# 04_-_LCD_VGA.net
KiCad netlist of a schematic drawn in Altium Designer
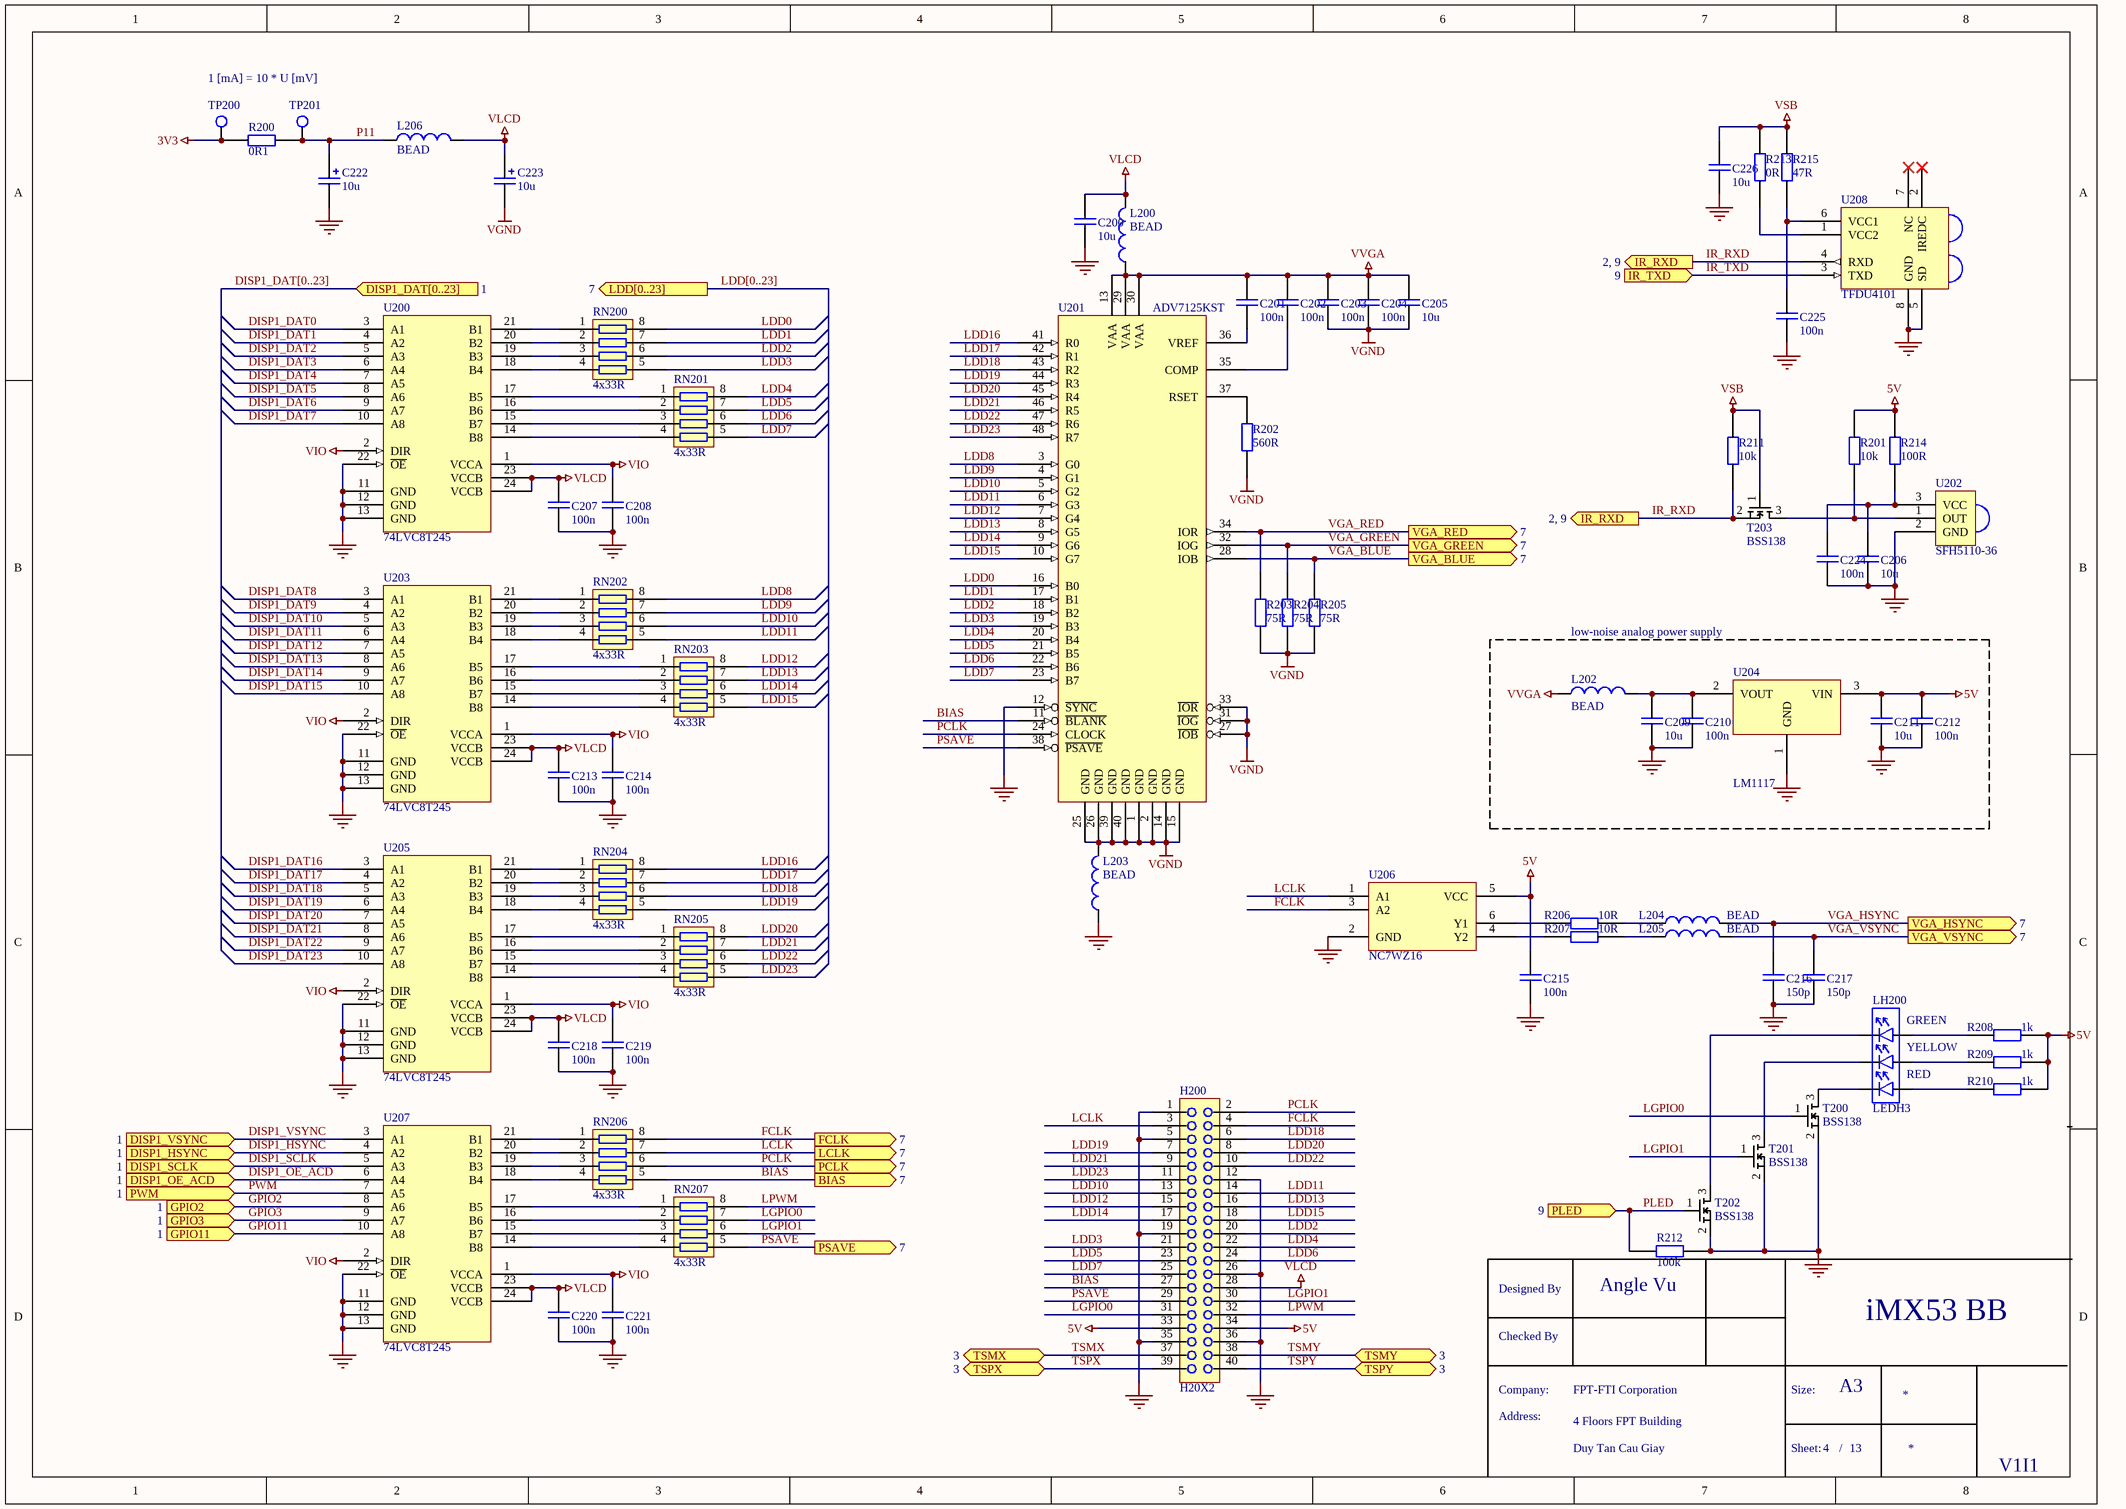
[diagram p0: [04] - LCD, VGA.SchDoc]

(export (version "E")
  (design (tool "Eeschema 10.0.6"))
  (components
    (comp (ref "C200") (value "10u") (footprint "0805") (libsource (lib "imxbb") (part "C")))
    (comp (ref "C201") (value "100n") (footprint "0603") (libsource (lib "imxbb") (part "C")))
    (comp (ref "C202") (value "100n") (footprint "0603") (libsource (lib "imxbb") (part "C")))
    (comp (ref "C203") (value "100n") (footprint "0603") (libsource (lib "imxbb") (part "C")))
    (comp (ref "C204") (value "100n") (footprint "0603") (libsource (lib "imxbb") (part "C")))
    (comp (ref "C205") (value "10u") (footprint "0805") (libsource (lib "imxbb") (part "C")))
    (comp (ref "C206") (value "10u") (footprint "0805") (libsource (lib "imxbb") (part "C")))
    (comp (ref "C207") (value "100n") (footprint "0603") (libsource (lib "imxbb") (part "C")))
    (comp (ref "C208") (value "100n") (footprint "0603") (libsource (lib "imxbb") (part "C")))
    (comp (ref "C209") (value "10u") (footprint "0805") (libsource (lib "imxbb") (part "C")))
    (comp (ref "C210") (value "100n") (footprint "0603") (libsource (lib "imxbb") (part "C")))
    (comp (ref "C211") (value "10u") (footprint "0805") (libsource (lib "imxbb") (part "C")))
    (comp (ref "C212") (value "100n") (footprint "0603") (libsource (lib "imxbb") (part "C")))
    (comp (ref "C213") (value "100n") (footprint "0603") (libsource (lib "imxbb") (part "C")))
    (comp (ref "C214") (value "100n") (footprint "0603") (libsource (lib "imxbb") (part "C")))
    (comp (ref "C215") (value "100n") (footprint "0603") (libsource (lib "imxbb") (part "C")))
    (comp (ref "C216") (value "150p") (footprint "0603") (libsource (lib "imxbb") (part "C")))
    (comp (ref "C217") (value "150p") (footprint "0603") (libsource (lib "imxbb") (part "C")))
    (comp (ref "C218") (value "100n") (footprint "0603") (libsource (lib "imxbb") (part "C")))
    (comp (ref "C219") (value "100n") (footprint "0603") (libsource (lib "imxbb") (part "C")))
    (comp (ref "C220") (value "100n") (footprint "0603") (libsource (lib "imxbb") (part "C")))
    (comp (ref "C221") (value "100n") (footprint "0603") (libsource (lib "imxbb") (part "C")))
    (comp (ref "C222") (value "10u") (footprint "3216A") (libsource (lib "imxbb") (part "C+")))
    (comp (ref "C223") (value "10u") (footprint "3216A") (libsource (lib "imxbb") (part "C+")))
    (comp (ref "C224") (value "100n") (footprint "0603") (libsource (lib "imxbb") (part "C")))
    (comp (ref "C225") (value "100n") (footprint "0603") (libsource (lib "imxbb") (part "C")))
    (comp (ref "C226") (value "10u") (footprint "0805") (libsource (lib "imxbb") (part "C")))
    (comp (ref "H200") (value "H20X2") (footprint "H2x20") (libsource (lib "imxbb") (part "H20X2")))
    (comp (ref "L200") (value "BEAD") (footprint "0603") (libsource (lib "imxbb") (part "FBEAD")))
    (comp (ref "L202") (value "BEAD") (footprint "0603") (libsource (lib "imxbb") (part "FBEAD")))
    (comp (ref "L203") (value "BEAD") (footprint "0603") (libsource (lib "imxbb") (part "FBEAD")))
    (comp (ref "L204") (value "BEAD") (footprint "0603") (libsource (lib "imxbb") (part "FBEAD")))
    (comp (ref "L205") (value "BEAD") (footprint "0603") (libsource (lib "imxbb") (part "FBEAD")))
    (comp (ref "L206") (value "BEAD") (footprint "0603") (libsource (lib "") (part "FBEAD_1")))
    (comp (ref "LH200") (value "LEDH3") (footprint "LED HOLDER 3") (libsource (lib "imxbb") (part "LEDH3")))
    (comp (ref "R200") (value "0R1") (footprint "0603") (libsource (lib "") (part "R_1")))
    (comp (ref "R201") (value "10k") (footprint "0603") (libsource (lib "") (part "R_3")))
    (comp (ref "R202") (value "560R") (footprint "0603") (libsource (lib "imxbb") (part "R")))
    (comp (ref "R203") (value "75R") (footprint "0603") (libsource (lib "imxbb") (part "R")))
    (comp (ref "R204") (value "75R") (footprint "0603") (libsource (lib "imxbb") (part "R")))
    (comp (ref "R205") (value "75R") (footprint "0603") (libsource (lib "imxbb") (part "R")))
    (comp (ref "R206") (value "10R") (footprint "0603") (libsource (lib "") (part "R_2")))
    (comp (ref "R207") (value "10R") (footprint "0603") (libsource (lib "") (part "R_2")))
    (comp (ref "R208") (value "1k") (footprint "0603") (libsource (lib "") (part "R_2")))
    (comp (ref "R209") (value "1k") (footprint "0603") (libsource (lib "") (part "R_2")))
    (comp (ref "R210") (value "1k") (footprint "0603") (libsource (lib "") (part "R_2")))
    (comp (ref "R211") (value "10k") (footprint "0603") (libsource (lib "") (part "R_3")))
    (comp (ref "R212") (value "100k") (footprint "0603") (libsource (lib "") (part "R_1")))
    (comp (ref "R213") (value "0R") (footprint "0603") (libsource (lib "imxbb") (part "R")))
    (comp (ref "R214") (value "100R") (footprint "0603") (libsource (lib "") (part "R_3")))
    (comp (ref "R215") (value "47R") (footprint "0603") (libsource (lib "") (part "R_3")))
    (comp (ref "RN200") (value "4x33R") (footprint "RX4_NS") (libsource (lib "imxbb") (part "RN4")))
    (comp (ref "RN201") (value "4x33R") (footprint "RX4_NS") (libsource (lib "imxbb") (part "RN4")))
    (comp (ref "RN202") (value "4x33R") (footprint "RX4_NS") (libsource (lib "imxbb") (part "RN4")))
    (comp (ref "RN203") (value "4x33R") (footprint "RX4_NS") (libsource (lib "imxbb") (part "RN4")))
    (comp (ref "RN204") (value "4x33R") (footprint "RX4_NS") (libsource (lib "imxbb") (part "RN4")))
    (comp (ref "RN205") (value "4x33R") (footprint "RX4_NS") (libsource (lib "imxbb") (part "RN4")))
    (comp (ref "RN206") (value "4x33R") (footprint "RX4_NS") (libsource (lib "imxbb") (part "RN4")))
    (comp (ref "RN207") (value "4x33R") (footprint "RX4_NS") (libsource (lib "imxbb") (part "RN4")))
    (comp (ref "T200") (value "BSS138") (footprint "SOT23") (libsource (lib "imxbb") (part "BSS138")))
    (comp (ref "T201") (value "BSS138") (footprint "SOT23") (libsource (lib "imxbb") (part "BSS138")))
    (comp (ref "T202") (value "BSS138") (footprint "SOT23") (libsource (lib "imxbb") (part "BSS138")))
    (comp (ref "T203") (value "BSS138") (footprint "SOT23") (libsource (lib "imxbb") (part "BSS138")))
    (comp (ref "TP200")
      (value "TESTPOINT")
      (footprint "TESTPOINT_2mm")
      (description "Testpoint pad")
      (libsource (lib "imxbb") (part "TESTPOINT"))
    )
    (comp (ref "TP201")
      (value "TESTPOINT")
      (footprint "TESTPOINT_2mm")
      (description "Testpoint pad")
      (libsource (lib "imxbb") (part "TESTPOINT"))
    )
    (comp (ref "U200")
      (value "74LVC8T245")
      (footprint "TSSOP24")
      (libsource (lib "imxbb") (part "74LVC8T245"))
    )
    (comp (ref "U201") (value "ADV7125KST") (footprint "LQFP48") (libsource (lib "imxbb") (part "ADV7125")))
    (comp (ref "U202") (value "SFH5110-36") (footprint "SFH511x") (libsource (lib "imxbb") (part "SFH5110")))
    (comp (ref "U203")
      (value "74LVC8T245")
      (footprint "TSSOP24")
      (libsource (lib "imxbb") (part "74LVC8T245"))
    )
    (comp (ref "U204") (value "LM1117") (footprint "SOT223") (libsource (lib "imxbb") (part "LM1117")))
    (comp (ref "U205")
      (value "74LVC8T245")
      (footprint "TSSOP24")
      (libsource (lib "imxbb") (part "74LVC8T245"))
    )
    (comp (ref "U206") (value "NC7WZ16") (footprint "SC70") (libsource (lib "imxbb") (part "NC7WZ16")))
    (comp (ref "U207")
      (value "74LVC8T245")
      (footprint "TSSOP24")
      (libsource (lib "imxbb") (part "74LVC8T245"))
    )
    (comp (ref "U208") (value "TFDU4101") (footprint "TDFU4101") (libsource (lib "imxbb") (part "TFDU4101")))
  )
  (nets
    (net (code "1") (name "/BIAS") (class "Default")
      (node (ref "H200") (pin "27") (pinfunction "27_27") (pintype "passive"))
      (node (ref "RN206") (pin "5") (pintype "passive"))
      (node (ref "U201") (pin "11") (pinfunction "~{BLANK}_11") (pintype "input"))
    )
    (net (code "2") (name "/DISP1_DAT0") (class "Default")
      (node (ref "U200") (pin "3") (pinfunction "A1_3") (pintype "passive"))
    )
    (net (code "3") (name "/DISP1_DAT1") (class "Default")
      (node (ref "U200") (pin "4") (pinfunction "A2_4") (pintype "passive"))
    )
    (net (code "4") (name "/DISP1_DAT2") (class "Default")
      (node (ref "U200") (pin "5") (pinfunction "A3_5") (pintype "passive"))
    )
    (net (code "5") (name "/DISP1_DAT3") (class "Default")
      (node (ref "U200") (pin "6") (pinfunction "A4_6") (pintype "passive"))
    )
    (net (code "6") (name "/DISP1_DAT4") (class "Default")
      (node (ref "U200") (pin "7") (pinfunction "A5_7") (pintype "passive"))
    )
    (net (code "7") (name "/DISP1_DAT5") (class "Default")
      (node (ref "U200") (pin "8") (pinfunction "A6_8") (pintype "passive"))
    )
    (net (code "8") (name "/DISP1_DAT6") (class "Default")
      (node (ref "U200") (pin "9") (pinfunction "A7_9") (pintype "passive"))
    )
    (net (code "9") (name "/DISP1_DAT7") (class "Default")
      (node (ref "U200") (pin "10") (pinfunction "A8_10") (pintype "passive"))
    )
    (net (code "10") (name "/DISP1_DAT8") (class "Default")
      (node (ref "U203") (pin "3") (pinfunction "A1_3") (pintype "passive"))
    )
    (net (code "11") (name "/DISP1_DAT9") (class "Default")
      (node (ref "U203") (pin "4") (pinfunction "A2_4") (pintype "passive"))
    )
    (net (code "12") (name "/DISP1_DAT10") (class "Default")
      (node (ref "U203") (pin "5") (pinfunction "A3_5") (pintype "passive"))
    )
    (net (code "13") (name "/DISP1_DAT11") (class "Default")
      (node (ref "U203") (pin "6") (pinfunction "A4_6") (pintype "passive"))
    )
    (net (code "14") (name "/DISP1_DAT12") (class "Default")
      (node (ref "U203") (pin "7") (pinfunction "A5_7") (pintype "passive"))
    )
    (net (code "15") (name "/DISP1_DAT13") (class "Default")
      (node (ref "U203") (pin "8") (pinfunction "A6_8") (pintype "passive"))
    )
    (net (code "16") (name "/DISP1_DAT14") (class "Default")
      (node (ref "U203") (pin "9") (pinfunction "A7_9") (pintype "passive"))
    )
    (net (code "17") (name "/DISP1_DAT15") (class "Default")
      (node (ref "U203") (pin "10") (pinfunction "A8_10") (pintype "passive"))
    )
    (net (code "18") (name "/DISP1_DAT16") (class "Default")
      (node (ref "U205") (pin "3") (pinfunction "A1_3") (pintype "passive"))
    )
    (net (code "19") (name "/DISP1_DAT17") (class "Default")
      (node (ref "U205") (pin "4") (pinfunction "A2_4") (pintype "passive"))
    )
    (net (code "20") (name "/DISP1_DAT18") (class "Default")
      (node (ref "U205") (pin "5") (pinfunction "A3_5") (pintype "passive"))
    )
    (net (code "21") (name "/DISP1_DAT19") (class "Default")
      (node (ref "U205") (pin "6") (pinfunction "A4_6") (pintype "passive"))
    )
    (net (code "22") (name "/DISP1_DAT20") (class "Default")
      (node (ref "U205") (pin "7") (pinfunction "A5_7") (pintype "passive"))
    )
    (net (code "23") (name "/DISP1_DAT21") (class "Default")
      (node (ref "U205") (pin "8") (pinfunction "A6_8") (pintype "passive"))
    )
    (net (code "24") (name "/DISP1_DAT22") (class "Default")
      (node (ref "U205") (pin "9") (pinfunction "A7_9") (pintype "passive"))
    )
    (net (code "25") (name "/DISP1_DAT23") (class "Default")
      (node (ref "U205") (pin "10") (pinfunction "A8_10") (pintype "passive"))
    )
    (net (code "27") (name "/DISP1_HSYNC") (class "Default")
      (node (ref "U207") (pin "4") (pinfunction "A2_4") (pintype "passive"))
    )
    (net (code "28") (name "/DISP1_OE_ACD") (class "Default")
      (node (ref "U207") (pin "6") (pinfunction "A4_6") (pintype "passive"))
    )
    (net (code "29") (name "/DISP1_SCLK") (class "Default")
      (node (ref "U207") (pin "5") (pinfunction "A3_5") (pintype "passive"))
    )
    (net (code "30") (name "/DISP1_VSYNC") (class "Default")
      (node (ref "U207") (pin "3") (pinfunction "A1_3") (pintype "passive"))
    )
    (net (code "31") (name "/FCLK") (class "Default")
      (node (ref "H200") (pin "4") (pinfunction "4_4") (pintype "passive"))
      (node (ref "RN206") (pin "8") (pintype "passive"))
      (node (ref "U206") (pin "3") (pinfunction "A2_3") (pintype "passive"))
    )
    (net (code "32") (name "/GPIO2") (class "Default")
      (node (ref "U207") (pin "8") (pinfunction "A6_8") (pintype "passive"))
    )
    (net (code "33") (name "/GPIO3") (class "Default")
      (node (ref "U207") (pin "9") (pinfunction "A7_9") (pintype "passive"))
    )
    (net (code "34") (name "/GPIO11") (class "Default")
      (node (ref "U207") (pin "10") (pinfunction "A8_10") (pintype "passive"))
    )
    (net (code "35") (name "/IR_RXD") (class "Default")
      (node (ref "R211") (pin "2") (pinfunction "2_2") (pintype "passive"))
      (node (ref "T203") (pin "2") (pinfunction "S_2") (pintype "passive"))
      (node (ref "U208") (pin "4") (pinfunction "RXD_4") (pintype "output"))
    )
    (net (code "36") (name "/IR_TXD") (class "Default")
      (node (ref "U208") (pin "3") (pinfunction "TXD_3") (pintype "input"))
    )
    (net (code "37") (name "/LCLK") (class "Default")
      (node (ref "H200") (pin "3") (pinfunction "3_3") (pintype "passive"))
      (node (ref "RN206") (pin "7") (pintype "passive"))
      (node (ref "U206") (pin "1") (pinfunction "A1_1") (pintype "passive"))
    )
    (net (code "38") (name "/LDD0") (class "Default")
      (node (ref "RN200") (pin "8") (pintype "passive"))
      (node (ref "U201") (pin "16") (pinfunction "B0_16") (pintype "input"))
    )
    (net (code "39") (name "/LDD1") (class "Default")
      (node (ref "RN200") (pin "7") (pintype "passive"))
      (node (ref "U201") (pin "17") (pinfunction "B1_17") (pintype "input"))
    )
    (net (code "40") (name "/LDD2") (class "Default")
      (node (ref "H200") (pin "20") (pinfunction "20_20") (pintype "passive"))
      (node (ref "RN200") (pin "6") (pintype "passive"))
      (node (ref "U201") (pin "18") (pinfunction "B2_18") (pintype "input"))
    )
    (net (code "41") (name "/LDD3") (class "Default")
      (node (ref "H200") (pin "21") (pinfunction "21_21") (pintype "passive"))
      (node (ref "RN200") (pin "5") (pintype "passive"))
      (node (ref "U201") (pin "19") (pinfunction "B3_19") (pintype "input"))
    )
    (net (code "42") (name "/LDD4") (class "Default")
      (node (ref "H200") (pin "22") (pinfunction "22_22") (pintype "passive"))
      (node (ref "RN201") (pin "8") (pintype "passive"))
      (node (ref "U201") (pin "20") (pinfunction "B4_20") (pintype "input"))
    )
    (net (code "43") (name "/LDD5") (class "Default")
      (node (ref "H200") (pin "23") (pinfunction "23_23") (pintype "passive"))
      (node (ref "RN201") (pin "7") (pintype "passive"))
      (node (ref "U201") (pin "21") (pinfunction "B5_21") (pintype "input"))
    )
    (net (code "44") (name "/LDD6") (class "Default")
      (node (ref "H200") (pin "24") (pinfunction "24_24") (pintype "passive"))
      (node (ref "RN201") (pin "6") (pintype "passive"))
      (node (ref "U201") (pin "22") (pinfunction "B6_22") (pintype "input"))
    )
    (net (code "45") (name "/LDD7") (class "Default")
      (node (ref "H200") (pin "25") (pinfunction "25_25") (pintype "passive"))
      (node (ref "RN201") (pin "5") (pintype "passive"))
      (node (ref "U201") (pin "23") (pinfunction "B7_23") (pintype "input"))
    )
    (net (code "46") (name "/LDD8") (class "Default")
      (node (ref "RN202") (pin "8") (pintype "passive"))
      (node (ref "U201") (pin "3") (pinfunction "G0_3") (pintype "input"))
    )
    (net (code "47") (name "/LDD9") (class "Default")
      (node (ref "RN202") (pin "7") (pintype "passive"))
      (node (ref "U201") (pin "4") (pinfunction "G1_4") (pintype "input"))
    )
    (net (code "48") (name "/LDD10") (class "Default")
      (node (ref "H200") (pin "13") (pinfunction "13_13") (pintype "passive"))
      (node (ref "RN202") (pin "6") (pintype "passive"))
      (node (ref "U201") (pin "5") (pinfunction "G2_5") (pintype "input"))
    )
    (net (code "49") (name "/LDD11") (class "Default")
      (node (ref "H200") (pin "14") (pinfunction "14_14") (pintype "passive"))
      (node (ref "RN202") (pin "5") (pintype "passive"))
      (node (ref "U201") (pin "6") (pinfunction "G3_6") (pintype "input"))
    )
    (net (code "50") (name "/LDD12") (class "Default")
      (node (ref "H200") (pin "15") (pinfunction "15_15") (pintype "passive"))
      (node (ref "RN203") (pin "8") (pintype "passive"))
      (node (ref "U201") (pin "7") (pinfunction "G4_7") (pintype "input"))
    )
    (net (code "51") (name "/LDD13") (class "Default")
      (node (ref "H200") (pin "16") (pinfunction "16_16") (pintype "passive"))
      (node (ref "RN203") (pin "7") (pintype "passive"))
      (node (ref "U201") (pin "8") (pinfunction "G5_8") (pintype "input"))
    )
    (net (code "52") (name "/LDD14") (class "Default")
      (node (ref "H200") (pin "17") (pinfunction "17_17") (pintype "passive"))
      (node (ref "RN203") (pin "6") (pintype "passive"))
      (node (ref "U201") (pin "9") (pinfunction "G6_9") (pintype "input"))
    )
    (net (code "53") (name "/LDD15") (class "Default")
      (node (ref "H200") (pin "18") (pinfunction "18_18") (pintype "passive"))
      (node (ref "RN203") (pin "5") (pintype "passive"))
      (node (ref "U201") (pin "10") (pinfunction "G7_10") (pintype "input"))
    )
    (net (code "54") (name "/LDD16") (class "Default")
      (node (ref "RN204") (pin "8") (pintype "passive"))
      (node (ref "U201") (pin "41") (pinfunction "R0_41") (pintype "input"))
    )
    (net (code "55") (name "/LDD17") (class "Default")
      (node (ref "RN204") (pin "7") (pintype "passive"))
      (node (ref "U201") (pin "42") (pinfunction "R1_42") (pintype "input"))
    )
    (net (code "56") (name "/LDD18") (class "Default")
      (node (ref "H200") (pin "6") (pinfunction "6_6") (pintype "passive"))
      (node (ref "RN204") (pin "6") (pintype "passive"))
      (node (ref "U201") (pin "43") (pinfunction "R2_43") (pintype "input"))
    )
    (net (code "57") (name "/LDD19") (class "Default")
      (node (ref "H200") (pin "7") (pinfunction "7_7") (pintype "passive"))
      (node (ref "RN204") (pin "5") (pintype "passive"))
      (node (ref "U201") (pin "44") (pinfunction "R3_44") (pintype "input"))
    )
    (net (code "58") (name "/LDD20") (class "Default")
      (node (ref "H200") (pin "8") (pinfunction "8_8") (pintype "passive"))
      (node (ref "RN205") (pin "8") (pintype "passive"))
      (node (ref "U201") (pin "45") (pinfunction "R4_45") (pintype "input"))
    )
    (net (code "59") (name "/LDD21") (class "Default")
      (node (ref "H200") (pin "9") (pinfunction "9_9") (pintype "passive"))
      (node (ref "RN205") (pin "7") (pintype "passive"))
      (node (ref "U201") (pin "46") (pinfunction "R5_46") (pintype "input"))
    )
    (net (code "60") (name "/LDD22") (class "Default")
      (node (ref "H200") (pin "10") (pinfunction "10_10") (pintype "passive"))
      (node (ref "RN205") (pin "6") (pintype "passive"))
      (node (ref "U201") (pin "47") (pinfunction "R6_47") (pintype "input"))
    )
    (net (code "61") (name "/LDD23") (class "Default")
      (node (ref "H200") (pin "11") (pinfunction "11_11") (pintype "passive"))
      (node (ref "RN205") (pin "5") (pintype "passive"))
      (node (ref "U201") (pin "48") (pinfunction "R7_48") (pintype "input"))
    )
    (net (code "63") (name "/LGPIO0") (class "Default")
      (node (ref "H200") (pin "31") (pinfunction "31_31") (pintype "passive"))
      (node (ref "RN207") (pin "7") (pintype "passive"))
      (node (ref "T200") (pin "1") (pinfunction "G_1") (pintype "passive"))
    )
    (net (code "64") (name "/LGPIO1") (class "Default")
      (node (ref "H200") (pin "30") (pinfunction "30_30") (pintype "passive"))
      (node (ref "RN207") (pin "6") (pintype "passive"))
      (node (ref "T201") (pin "1") (pinfunction "G_1") (pintype "passive"))
    )
    (net (code "65") (name "/LPWM") (class "Default")
      (node (ref "H200") (pin "32") (pinfunction "32_32") (pintype "passive"))
      (node (ref "RN207") (pin "8") (pintype "passive"))
    )
    (net (code "66") (name "/P11") (class "Default")
      (node (ref "C222") (pin "1") (pinfunction "1_1") (pintype "passive"))
      (node (ref "L206") (pin "2") (pinfunction "2_2") (pintype "passive"))
      (node (ref "R200") (pin "2") (pinfunction "2_2") (pintype "passive"))
      (node (ref "TP201") (pin "1") (pinfunction "1_1") (pintype "passive"))
    )
    (net (code "67") (name "/PCLK") (class "Default")
      (node (ref "H200") (pin "2") (pinfunction "2_2") (pintype "passive"))
      (node (ref "RN206") (pin "6") (pintype "passive"))
      (node (ref "U201") (pin "24") (pinfunction "CLOCK_24") (pintype "input"))
    )
    (net (code "68") (name "/PLED") (class "Default")
      (node (ref "R212") (pin "1") (pinfunction "1_1") (pintype "passive"))
      (node (ref "T202") (pin "1") (pinfunction "G_1") (pintype "passive"))
    )
    (net (code "69") (name "/PSAVE") (class "Default")
      (node (ref "H200") (pin "29") (pinfunction "29_29") (pintype "passive"))
      (node (ref "RN207") (pin "5") (pintype "passive"))
      (node (ref "U201") (pin "38") (pinfunction "~{PSAVE}_38") (pintype "input"))
    )
    (net (code "70") (name "/PWM") (class "Default")
      (node (ref "U207") (pin "7") (pinfunction "A5_7") (pintype "passive"))
    )
    (net (code "71") (name "/TSMX") (class "Default")
      (node (ref "H200") (pin "37") (pinfunction "37_37") (pintype "passive"))
    )
    (net (code "72") (name "/TSMY") (class "Default")
      (node (ref "H200") (pin "38") (pinfunction "38_38") (pintype "passive"))
    )
    (net (code "73") (name "/TSPX") (class "Default")
      (node (ref "H200") (pin "39") (pinfunction "39_39") (pintype "passive"))
    )
    (net (code "74") (name "/TSPY") (class "Default")
      (node (ref "H200") (pin "40") (pinfunction "40_40") (pintype "passive"))
    )
    (net (code "75") (name "/VGA_BLUE") (class "Default")
      (node (ref "R205") (pin "2") (pinfunction "2_2") (pintype "passive"))
      (node (ref "U201") (pin "28") (pinfunction "IOB_28") (pintype "output"))
    )
    (net (code "76") (name "/VGA_GREEN") (class "Default")
      (node (ref "R204") (pin "2") (pinfunction "2_2") (pintype "passive"))
      (node (ref "U201") (pin "32") (pinfunction "IOG_32") (pintype "output"))
    )
    (net (code "77") (name "/VGA_HSYNC") (class "Default")
      (node (ref "C216") (pin "2") (pinfunction "2_2") (pintype "passive"))
      (node (ref "L204") (pin "2") (pinfunction "2_2") (pintype "passive"))
    )
    (net (code "78") (name "/VGA_RED") (class "Default")
      (node (ref "R203") (pin "2") (pinfunction "2_2") (pintype "passive"))
      (node (ref "U201") (pin "34") (pinfunction "IOR_34") (pintype "output"))
    )
    (net (code "79") (name "/VGA_VSYNC") (class "Default")
      (node (ref "C217") (pin "2") (pinfunction "2_2") (pintype "passive"))
      (node (ref "L205") (pin "2") (pinfunction "2_2") (pintype "passive"))
    )
    (net (code "80") (name "3V3") (class "Default")
      (node (ref "R200") (pin "1") (pinfunction "1_1") (pintype "passive"))
      (node (ref "TP200") (pin "1") (pinfunction "1_1") (pintype "passive"))
    )
    (net (code "81") (name "5V") (class "Default")
      (node (ref "C211") (pin "2") (pinfunction "2_2") (pintype "passive"))
      (node (ref "C212") (pin "2") (pinfunction "2_2") (pintype "passive"))
      (node (ref "C215") (pin "2") (pinfunction "2_2") (pintype "passive"))
      (node (ref "H200") (pin "33") (pinfunction "33_33") (pintype "passive"))
      (node (ref "H200") (pin "34") (pinfunction "34_34") (pintype "passive"))
      (node (ref "R201") (pin "1") (pinfunction "1_1") (pintype "passive"))
      (node (ref "R208") (pin "1") (pinfunction "1_1") (pintype "passive"))
      (node (ref "R209") (pin "1") (pinfunction "1_1") (pintype "passive"))
      (node (ref "R210") (pin "1") (pinfunction "1_1") (pintype "passive"))
      (node (ref "R214") (pin "1") (pinfunction "1_1") (pintype "passive"))
      (node (ref "U204") (pin "3") (pinfunction "VIN_3") (pintype "passive"))
      (node (ref "U206") (pin "5") (pinfunction "VCC_5") (pintype "passive"))
    )
    (net (code "82") (name "GND") (class "Default")
      (node (ref "C200") (pin "1") (pinfunction "1_1") (pintype "passive"))
      (node (ref "C206") (pin "1") (pinfunction "1_1") (pintype "passive"))
      (node (ref "C207") (pin "1") (pinfunction "1_1") (pintype "passive"))
      (node (ref "C208") (pin "1") (pinfunction "1_1") (pintype "passive"))
      (node (ref "C209") (pin "1") (pinfunction "1_1") (pintype "passive"))
      (node (ref "C210") (pin "1") (pinfunction "1_1") (pintype "passive"))
      (node (ref "C211") (pin "1") (pinfunction "1_1") (pintype "passive"))
      (node (ref "C212") (pin "1") (pinfunction "1_1") (pintype "passive"))
      (node (ref "C213") (pin "1") (pinfunction "1_1") (pintype "passive"))
      (node (ref "C214") (pin "1") (pinfunction "1_1") (pintype "passive"))
      (node (ref "C215") (pin "1") (pinfunction "1_1") (pintype "passive"))
      (node (ref "C216") (pin "1") (pinfunction "1_1") (pintype "passive"))
      (node (ref "C217") (pin "1") (pinfunction "1_1") (pintype "passive"))
      (node (ref "C218") (pin "1") (pinfunction "1_1") (pintype "passive"))
      (node (ref "C219") (pin "1") (pinfunction "1_1") (pintype "passive"))
      (node (ref "C220") (pin "1") (pinfunction "1_1") (pintype "passive"))
      (node (ref "C221") (pin "1") (pinfunction "1_1") (pintype "passive"))
      (node (ref "C222") (pin "2") (pinfunction "2_2") (pintype "passive"))
      (node (ref "C224") (pin "1") (pinfunction "1_1") (pintype "passive"))
      (node (ref "C225") (pin "1") (pinfunction "1_1") (pintype "passive"))
      (node (ref "C226") (pin "1") (pinfunction "1_1") (pintype "passive"))
      (node (ref "H200") (pin "1") (pinfunction "1_1") (pintype "passive"))
      (node (ref "H200") (pin "12") (pinfunction "12_12") (pintype "passive"))
      (node (ref "H200") (pin "19") (pinfunction "19_19") (pintype "passive"))
      (node (ref "H200") (pin "26") (pinfunction "26_26") (pintype "passive"))
      (node (ref "H200") (pin "35") (pinfunction "35_35") (pintype "passive"))
      (node (ref "H200") (pin "36") (pinfunction "36_36") (pintype "passive"))
      (node (ref "H200") (pin "5") (pinfunction "5_5") (pintype "passive"))
      (node (ref "L203") (pin "1") (pinfunction "1_1") (pintype "passive"))
      (node (ref "R212") (pin "2") (pinfunction "2_2") (pintype "passive"))
      (node (ref "T200") (pin "2") (pinfunction "S_2") (pintype "passive"))
      (node (ref "T201") (pin "2") (pinfunction "S_2") (pintype "passive"))
      (node (ref "T202") (pin "2") (pinfunction "S_2") (pintype "passive"))
      (node (ref "U200") (pin "11") (pinfunction "GND_11") (pintype "power_in"))
      (node (ref "U200") (pin "12") (pinfunction "GND_12") (pintype "power_in"))
      (node (ref "U200") (pin "13") (pinfunction "GND_13") (pintype "power_in"))
      (node (ref "U200") (pin "22") (pinfunction "~{OE}_22") (pintype "input"))
      (node (ref "U201") (pin "12") (pinfunction "~{SYNC}_12") (pintype "input"))
      (node (ref "U202") (pin "2") (pinfunction "GND_2") (pintype "passive"))
      (node (ref "U203") (pin "11") (pinfunction "GND_11") (pintype "power_in"))
      (node (ref "U203") (pin "12") (pinfunction "GND_12") (pintype "power_in"))
      (node (ref "U203") (pin "13") (pinfunction "GND_13") (pintype "power_in"))
      (node (ref "U203") (pin "22") (pinfunction "~{OE}_22") (pintype "input"))
      (node (ref "U204") (pin "1") (pinfunction "GND_1") (pintype "passive"))
      (node (ref "U205") (pin "11") (pinfunction "GND_11") (pintype "power_in"))
      (node (ref "U205") (pin "12") (pinfunction "GND_12") (pintype "power_in"))
      (node (ref "U205") (pin "13") (pinfunction "GND_13") (pintype "power_in"))
      (node (ref "U205") (pin "22") (pinfunction "~{OE}_22") (pintype "input"))
      (node (ref "U206") (pin "2") (pinfunction "GND_2") (pintype "passive"))
      (node (ref "U207") (pin "11") (pinfunction "GND_11") (pintype "power_in"))
      (node (ref "U207") (pin "12") (pinfunction "GND_12") (pintype "power_in"))
      (node (ref "U207") (pin "13") (pinfunction "GND_13") (pintype "power_in"))
      (node (ref "U207") (pin "22") (pinfunction "~{OE}_22") (pintype "input"))
      (node (ref "U208") (pin "5") (pinfunction "SD_5") (pintype "passive"))
      (node (ref "U208") (pin "8") (pinfunction "GND_8") (pintype "passive"))
    )
    (net (code "83") (name "Net-(L204-Pad1)") (class "Default")
      (node (ref "L204") (pin "1") (pinfunction "1_1") (pintype "passive"))
      (node (ref "R206") (pin "1") (pinfunction "1_1") (pintype "passive"))
    )
    (net (code "84") (name "Net-(L205-Pad1)") (class "Default")
      (node (ref "L205") (pin "1") (pinfunction "1_1") (pintype "passive"))
      (node (ref "R207") (pin "1") (pinfunction "1_1") (pintype "passive"))
    )
    (net (code "85") (name "Net-(LH200-Pad2)") (class "Default")
      (node (ref "LH200") (pin "2") (pinfunction "2_2") (pintype "passive"))
      (node (ref "R208") (pin "2") (pinfunction "2_2") (pintype "passive"))
    )
    (net (code "86") (name "Net-(LH200-Pad4)") (class "Default")
      (node (ref "LH200") (pin "4") (pinfunction "4_4") (pintype "passive"))
      (node (ref "R209") (pin "2") (pinfunction "2_2") (pintype "passive"))
    )
    (net (code "87") (name "Net-(LH200-Pad6)") (class "Default")
      (node (ref "LH200") (pin "6") (pinfunction "6_6") (pintype "passive"))
      (node (ref "R210") (pin "2") (pinfunction "2_2") (pintype "passive"))
    )
    (net (code "88") (name "Net-(T200-D)") (class "Default")
      (node (ref "LH200") (pin "5") (pinfunction "5_5") (pintype "passive"))
      (node (ref "T200") (pin "3") (pinfunction "D_3") (pintype "passive"))
    )
    (net (code "89") (name "Net-(T201-D)") (class "Default")
      (node (ref "LH200") (pin "3") (pinfunction "3_3") (pintype "passive"))
      (node (ref "T201") (pin "3") (pinfunction "D_3") (pintype "passive"))
    )
    (net (code "90") (name "Net-(T202-D)") (class "Default")
      (node (ref "LH200") (pin "1") (pinfunction "1_1") (pintype "passive"))
      (node (ref "T202") (pin "3") (pinfunction "D_3") (pintype "passive"))
    )
    (net (code "91") (name "Net-(T203-D)") (class "Default")
      (node (ref "R201") (pin "2") (pinfunction "2_2") (pintype "passive"))
      (node (ref "T203") (pin "3") (pinfunction "D_3") (pintype "passive"))
      (node (ref "U202") (pin "1") (pinfunction "OUT_1") (pintype "passive"))
    )
    (net (code "92") (name "Net-(U200-B1)") (class "Default")
      (node (ref "RN200") (pin "1") (pintype "passive"))
      (node (ref "U200") (pin "21") (pinfunction "B1_21") (pintype "passive"))
    )
    (net (code "93") (name "Net-(U200-B2)") (class "Default")
      (node (ref "RN200") (pin "2") (pintype "passive"))
      (node (ref "U200") (pin "20") (pinfunction "B2_20") (pintype "passive"))
    )
    (net (code "94") (name "Net-(U200-B3)") (class "Default")
      (node (ref "RN200") (pin "3") (pintype "passive"))
      (node (ref "U200") (pin "19") (pinfunction "B3_19") (pintype "passive"))
    )
    (net (code "95") (name "Net-(U200-B4)") (class "Default")
      (node (ref "RN200") (pin "4") (pintype "passive"))
      (node (ref "U200") (pin "18") (pinfunction "B4_18") (pintype "passive"))
    )
    (net (code "96") (name "Net-(U200-B5)") (class "Default")
      (node (ref "RN201") (pin "1") (pintype "passive"))
      (node (ref "U200") (pin "17") (pinfunction "B5_17") (pintype "passive"))
    )
    (net (code "97") (name "Net-(U200-B6)") (class "Default")
      (node (ref "RN201") (pin "2") (pintype "passive"))
      (node (ref "U200") (pin "16") (pinfunction "B6_16") (pintype "passive"))
    )
    (net (code "98") (name "Net-(U200-B7)") (class "Default")
      (node (ref "RN201") (pin "3") (pintype "passive"))
      (node (ref "U200") (pin "15") (pinfunction "B7_15") (pintype "passive"))
    )
    (net (code "99") (name "Net-(U200-B8)") (class "Default")
      (node (ref "RN201") (pin "4") (pintype "passive"))
      (node (ref "U200") (pin "14") (pinfunction "B8_14") (pintype "passive"))
    )
    (net (code "100") (name "Net-(U201-COMP)") (class "Default")
      (node (ref "C202") (pin "1") (pinfunction "1_1") (pintype "passive"))
      (node (ref "U201") (pin "35") (pinfunction "COMP_35") (pintype "passive"))
    )
    (net (code "101") (name "Net-(U201-RSET)") (class "Default")
      (node (ref "R202") (pin "2") (pinfunction "2_2") (pintype "passive"))
      (node (ref "U201") (pin "37") (pinfunction "RSET_37") (pintype "passive"))
    )
    (net (code "102") (name "Net-(U201-VREF)") (class "Default")
      (node (ref "C201") (pin "1") (pinfunction "1_1") (pintype "passive"))
      (node (ref "U201") (pin "36") (pinfunction "VREF_36") (pintype "passive"))
    )
    (net (code "103") (name "Net-(U202-VCC)") (class "Default")
      (node (ref "C206") (pin "2") (pinfunction "2_2") (pintype "passive"))
      (node (ref "C224") (pin "2") (pinfunction "2_2") (pintype "passive"))
      (node (ref "R214") (pin "2") (pinfunction "2_2") (pintype "passive"))
      (node (ref "U202") (pin "3") (pinfunction "VCC_3") (pintype "passive"))
    )
    (net (code "104") (name "Net-(U203-B1)") (class "Default")
      (node (ref "RN202") (pin "1") (pintype "passive"))
      (node (ref "U203") (pin "21") (pinfunction "B1_21") (pintype "passive"))
    )
    (net (code "105") (name "Net-(U203-B2)") (class "Default")
      (node (ref "RN202") (pin "2") (pintype "passive"))
      (node (ref "U203") (pin "20") (pinfunction "B2_20") (pintype "passive"))
    )
    (net (code "106") (name "Net-(U203-B3)") (class "Default")
      (node (ref "RN202") (pin "3") (pintype "passive"))
      (node (ref "U203") (pin "19") (pinfunction "B3_19") (pintype "passive"))
    )
    (net (code "107") (name "Net-(U203-B4)") (class "Default")
      (node (ref "RN202") (pin "4") (pintype "passive"))
      (node (ref "U203") (pin "18") (pinfunction "B4_18") (pintype "passive"))
    )
    (net (code "108") (name "Net-(U203-B5)") (class "Default")
      (node (ref "RN203") (pin "1") (pintype "passive"))
      (node (ref "U203") (pin "17") (pinfunction "B5_17") (pintype "passive"))
    )
    (net (code "109") (name "Net-(U203-B6)") (class "Default")
      (node (ref "RN203") (pin "2") (pintype "passive"))
      (node (ref "U203") (pin "16") (pinfunction "B6_16") (pintype "passive"))
    )
    (net (code "110") (name "Net-(U203-B7)") (class "Default")
      (node (ref "RN203") (pin "3") (pintype "passive"))
      (node (ref "U203") (pin "15") (pinfunction "B7_15") (pintype "passive"))
    )
    (net (code "111") (name "Net-(U203-B8)") (class "Default")
      (node (ref "RN203") (pin "4") (pintype "passive"))
      (node (ref "U203") (pin "14") (pinfunction "B8_14") (pintype "passive"))
    )
    (net (code "112") (name "Net-(U204-VOUT)") (class "Default")
      (node (ref "C209") (pin "2") (pinfunction "2_2") (pintype "passive"))
      (node (ref "C210") (pin "2") (pinfunction "2_2") (pintype "passive"))
      (node (ref "L202") (pin "2") (pinfunction "2_2") (pintype "passive"))
      (node (ref "U204") (pin "2") (pinfunction "VOUT_2") (pintype "passive"))
    )
    (net (code "113") (name "Net-(U205-B1)") (class "Default")
      (node (ref "RN204") (pin "1") (pintype "passive"))
      (node (ref "U205") (pin "21") (pinfunction "B1_21") (pintype "passive"))
    )
    (net (code "114") (name "Net-(U205-B2)") (class "Default")
      (node (ref "RN204") (pin "2") (pintype "passive"))
      (node (ref "U205") (pin "20") (pinfunction "B2_20") (pintype "passive"))
    )
    (net (code "115") (name "Net-(U205-B3)") (class "Default")
      (node (ref "RN204") (pin "3") (pintype "passive"))
      (node (ref "U205") (pin "19") (pinfunction "B3_19") (pintype "passive"))
    )
    (net (code "116") (name "Net-(U205-B4)") (class "Default")
      (node (ref "RN204") (pin "4") (pintype "passive"))
      (node (ref "U205") (pin "18") (pinfunction "B4_18") (pintype "passive"))
    )
    (net (code "117") (name "Net-(U205-B5)") (class "Default")
      (node (ref "RN205") (pin "1") (pintype "passive"))
      (node (ref "U205") (pin "17") (pinfunction "B5_17") (pintype "passive"))
    )
    (net (code "118") (name "Net-(U205-B6)") (class "Default")
      (node (ref "RN205") (pin "2") (pintype "passive"))
      (node (ref "U205") (pin "16") (pinfunction "B6_16") (pintype "passive"))
    )
    (net (code "119") (name "Net-(U205-B7)") (class "Default")
      (node (ref "RN205") (pin "3") (pintype "passive"))
      (node (ref "U205") (pin "15") (pinfunction "B7_15") (pintype "passive"))
    )
    (net (code "120") (name "Net-(U205-B8)") (class "Default")
      (node (ref "RN205") (pin "4") (pintype "passive"))
      (node (ref "U205") (pin "14") (pinfunction "B8_14") (pintype "passive"))
    )
    (net (code "121") (name "Net-(U206-Y1)") (class "Default")
      (node (ref "R206") (pin "2") (pinfunction "2_2") (pintype "passive"))
      (node (ref "U206") (pin "6") (pinfunction "Y1_6") (pintype "passive"))
    )
    (net (code "122") (name "Net-(U206-Y2)") (class "Default")
      (node (ref "R207") (pin "2") (pinfunction "2_2") (pintype "passive"))
      (node (ref "U206") (pin "4") (pinfunction "Y2_4") (pintype "passive"))
    )
    (net (code "123") (name "Net-(U207-B1)") (class "Default")
      (node (ref "RN206") (pin "1") (pintype "passive"))
      (node (ref "U207") (pin "21") (pinfunction "B1_21") (pintype "passive"))
    )
    (net (code "124") (name "Net-(U207-B2)") (class "Default")
      (node (ref "RN206") (pin "2") (pintype "passive"))
      (node (ref "U207") (pin "20") (pinfunction "B2_20") (pintype "passive"))
    )
    (net (code "125") (name "Net-(U207-B3)") (class "Default")
      (node (ref "RN206") (pin "3") (pintype "passive"))
      (node (ref "U207") (pin "19") (pinfunction "B3_19") (pintype "passive"))
    )
    (net (code "126") (name "Net-(U207-B4)") (class "Default")
      (node (ref "RN206") (pin "4") (pintype "passive"))
      (node (ref "U207") (pin "18") (pinfunction "B4_18") (pintype "passive"))
    )
    (net (code "127") (name "Net-(U207-B5)") (class "Default")
      (node (ref "RN207") (pin "1") (pintype "passive"))
      (node (ref "U207") (pin "17") (pinfunction "B5_17") (pintype "passive"))
    )
    (net (code "128") (name "Net-(U207-B6)") (class "Default")
      (node (ref "RN207") (pin "2") (pintype "passive"))
      (node (ref "U207") (pin "16") (pinfunction "B6_16") (pintype "passive"))
    )
    (net (code "129") (name "Net-(U207-B7)") (class "Default")
      (node (ref "RN207") (pin "3") (pintype "passive"))
      (node (ref "U207") (pin "15") (pinfunction "B7_15") (pintype "passive"))
    )
    (net (code "130") (name "Net-(U207-B8)") (class "Default")
      (node (ref "RN207") (pin "4") (pintype "passive"))
      (node (ref "U207") (pin "14") (pinfunction "B8_14") (pintype "passive"))
    )
    (net (code "131") (name "Net-(U208-VCC1)") (class "Default")
      (node (ref "C225") (pin "2") (pinfunction "2_2") (pintype "passive"))
      (node (ref "R215") (pin "2") (pinfunction "2_2") (pintype "passive"))
      (node (ref "U208") (pin "6") (pinfunction "VCC1_6") (pintype "passive"))
    )
    (net (code "132") (name "Net-(U208-VCC2)") (class "Default")
      (node (ref "R213") (pin "1") (pinfunction "1_1") (pintype "passive"))
      (node (ref "U208") (pin "1") (pinfunction "VCC2_1") (pintype "passive"))
    )
    (net (code "133") (name "VGND") (class "Default")
      (node (ref "C203") (pin "1") (pinfunction "1_1") (pintype "passive"))
      (node (ref "C204") (pin "1") (pinfunction "1_1") (pintype "passive"))
      (node (ref "C205") (pin "1") (pinfunction "1_1") (pintype "passive"))
      (node (ref "C223") (pin "2") (pinfunction "2_2") (pintype "passive"))
      (node (ref "L203") (pin "2") (pinfunction "2_2") (pintype "passive"))
      (node (ref "R202") (pin "1") (pinfunction "1_1") (pintype "passive"))
      (node (ref "R203") (pin "1") (pinfunction "1_1") (pintype "passive"))
      (node (ref "R204") (pin "1") (pinfunction "1_1") (pintype "passive"))
      (node (ref "R205") (pin "1") (pinfunction "1_1") (pintype "passive"))
      (node (ref "U201") (pin "1") (pinfunction "GND_1") (pintype "power_in"))
      (node (ref "U201") (pin "14") (pinfunction "GND_14") (pintype "power_in"))
      (node (ref "U201") (pin "15") (pinfunction "GND_15") (pintype "power_in"))
      (node (ref "U201") (pin "2") (pinfunction "GND_2") (pintype "power_in"))
      (node (ref "U201") (pin "25") (pinfunction "GND_25") (pintype "power_in"))
      (node (ref "U201") (pin "26") (pinfunction "GND_26") (pintype "power_in"))
      (node (ref "U201") (pin "27") (pinfunction "~{IOB}_27") (pintype "input"))
      (node (ref "U201") (pin "31") (pinfunction "~{IOG}_31") (pintype "input"))
      (node (ref "U201") (pin "33") (pinfunction "~{IOR}_33") (pintype "input"))
      (node (ref "U201") (pin "39") (pinfunction "GND_39") (pintype "power_in"))
      (node (ref "U201") (pin "40") (pinfunction "GND_40") (pintype "power_in"))
    )
    (net (code "134") (name "VIO") (class "Default")
      (node (ref "C208") (pin "2") (pinfunction "2_2") (pintype "passive"))
      (node (ref "C214") (pin "2") (pinfunction "2_2") (pintype "passive"))
      (node (ref "C219") (pin "2") (pinfunction "2_2") (pintype "passive"))
      (node (ref "C221") (pin "2") (pinfunction "2_2") (pintype "passive"))
      (node (ref "U200") (pin "1") (pinfunction "VCCA_1") (pintype "power_in"))
      (node (ref "U200") (pin "2") (pinfunction "DIR_2") (pintype "input"))
      (node (ref "U203") (pin "1") (pinfunction "VCCA_1") (pintype "power_in"))
      (node (ref "U203") (pin "2") (pinfunction "DIR_2") (pintype "input"))
      (node (ref "U205") (pin "1") (pinfunction "VCCA_1") (pintype "power_in"))
      (node (ref "U205") (pin "2") (pinfunction "DIR_2") (pintype "input"))
      (node (ref "U207") (pin "1") (pinfunction "VCCA_1") (pintype "power_in"))
      (node (ref "U207") (pin "2") (pinfunction "DIR_2") (pintype "input"))
    )
    (net (code "135") (name "VLCD") (class "Default")
      (node (ref "C200") (pin "2") (pinfunction "2_2") (pintype "passive"))
      (node (ref "C207") (pin "2") (pinfunction "2_2") (pintype "passive"))
      (node (ref "C213") (pin "2") (pinfunction "2_2") (pintype "passive"))
      (node (ref "C218") (pin "2") (pinfunction "2_2") (pintype "passive"))
      (node (ref "C220") (pin "2") (pinfunction "2_2") (pintype "passive"))
      (node (ref "C223") (pin "1") (pinfunction "1_1") (pintype "passive"))
      (node (ref "H200") (pin "28") (pinfunction "28_28") (pintype "passive"))
      (node (ref "L200") (pin "2") (pinfunction "2_2") (pintype "passive"))
      (node (ref "L206") (pin "1") (pinfunction "1_1") (pintype "passive"))
      (node (ref "U200") (pin "23") (pinfunction "VCCB_23") (pintype "power_in"))
      (node (ref "U200") (pin "24") (pinfunction "VCCB_24") (pintype "power_in"))
      (node (ref "U203") (pin "23") (pinfunction "VCCB_23") (pintype "power_in"))
      (node (ref "U203") (pin "24") (pinfunction "VCCB_24") (pintype "power_in"))
      (node (ref "U205") (pin "23") (pinfunction "VCCB_23") (pintype "power_in"))
      (node (ref "U205") (pin "24") (pinfunction "VCCB_24") (pintype "power_in"))
      (node (ref "U207") (pin "23") (pinfunction "VCCB_23") (pintype "power_in"))
      (node (ref "U207") (pin "24") (pinfunction "VCCB_24") (pintype "power_in"))
    )
    (net (code "136") (name "VSB") (class "Default")
      (node (ref "C226") (pin "2") (pinfunction "2_2") (pintype "passive"))
      (node (ref "R211") (pin "1") (pinfunction "1_1") (pintype "passive"))
      (node (ref "R213") (pin "2") (pinfunction "2_2") (pintype "passive"))
      (node (ref "R215") (pin "1") (pinfunction "1_1") (pintype "passive"))
      (node (ref "T203") (pin "1") (pinfunction "G_1") (pintype "passive"))
    )
    (net (code "137") (name "VVGA") (class "Default")
      (node (ref "C201") (pin "2") (pinfunction "2_2") (pintype "passive"))
      (node (ref "C202") (pin "2") (pinfunction "2_2") (pintype "passive"))
      (node (ref "C203") (pin "2") (pinfunction "2_2") (pintype "passive"))
      (node (ref "C204") (pin "2") (pinfunction "2_2") (pintype "passive"))
      (node (ref "C205") (pin "2") (pinfunction "2_2") (pintype "passive"))
      (node (ref "L200") (pin "1") (pinfunction "1_1") (pintype "passive"))
      (node (ref "L202") (pin "1") (pinfunction "1_1") (pintype "passive"))
      (node (ref "U201") (pin "13") (pinfunction "VAA_13") (pintype "power_in"))
      (node (ref "U201") (pin "29") (pinfunction "VAA_29") (pintype "power_in"))
      (node (ref "U201") (pin "30") (pinfunction "VAA_30") (pintype "power_in"))
    )
    (net (code "138") (name "unconnected-(U208-IREDC-Pad2)") (class "Default")
      (node (ref "U208") (pin "2") (pinfunction "IREDC_2") (pintype "passive+no_connect"))
    )
    (net (code "139") (name "unconnected-(U208-NC-Pad7)") (class "Default")
      (node (ref "U208") (pin "7") (pinfunction "NC_7") (pintype "passive+no_connect"))
    )
  )
)
